# M207X.net
KiCad netlist of a schematic drawn in EAGLE
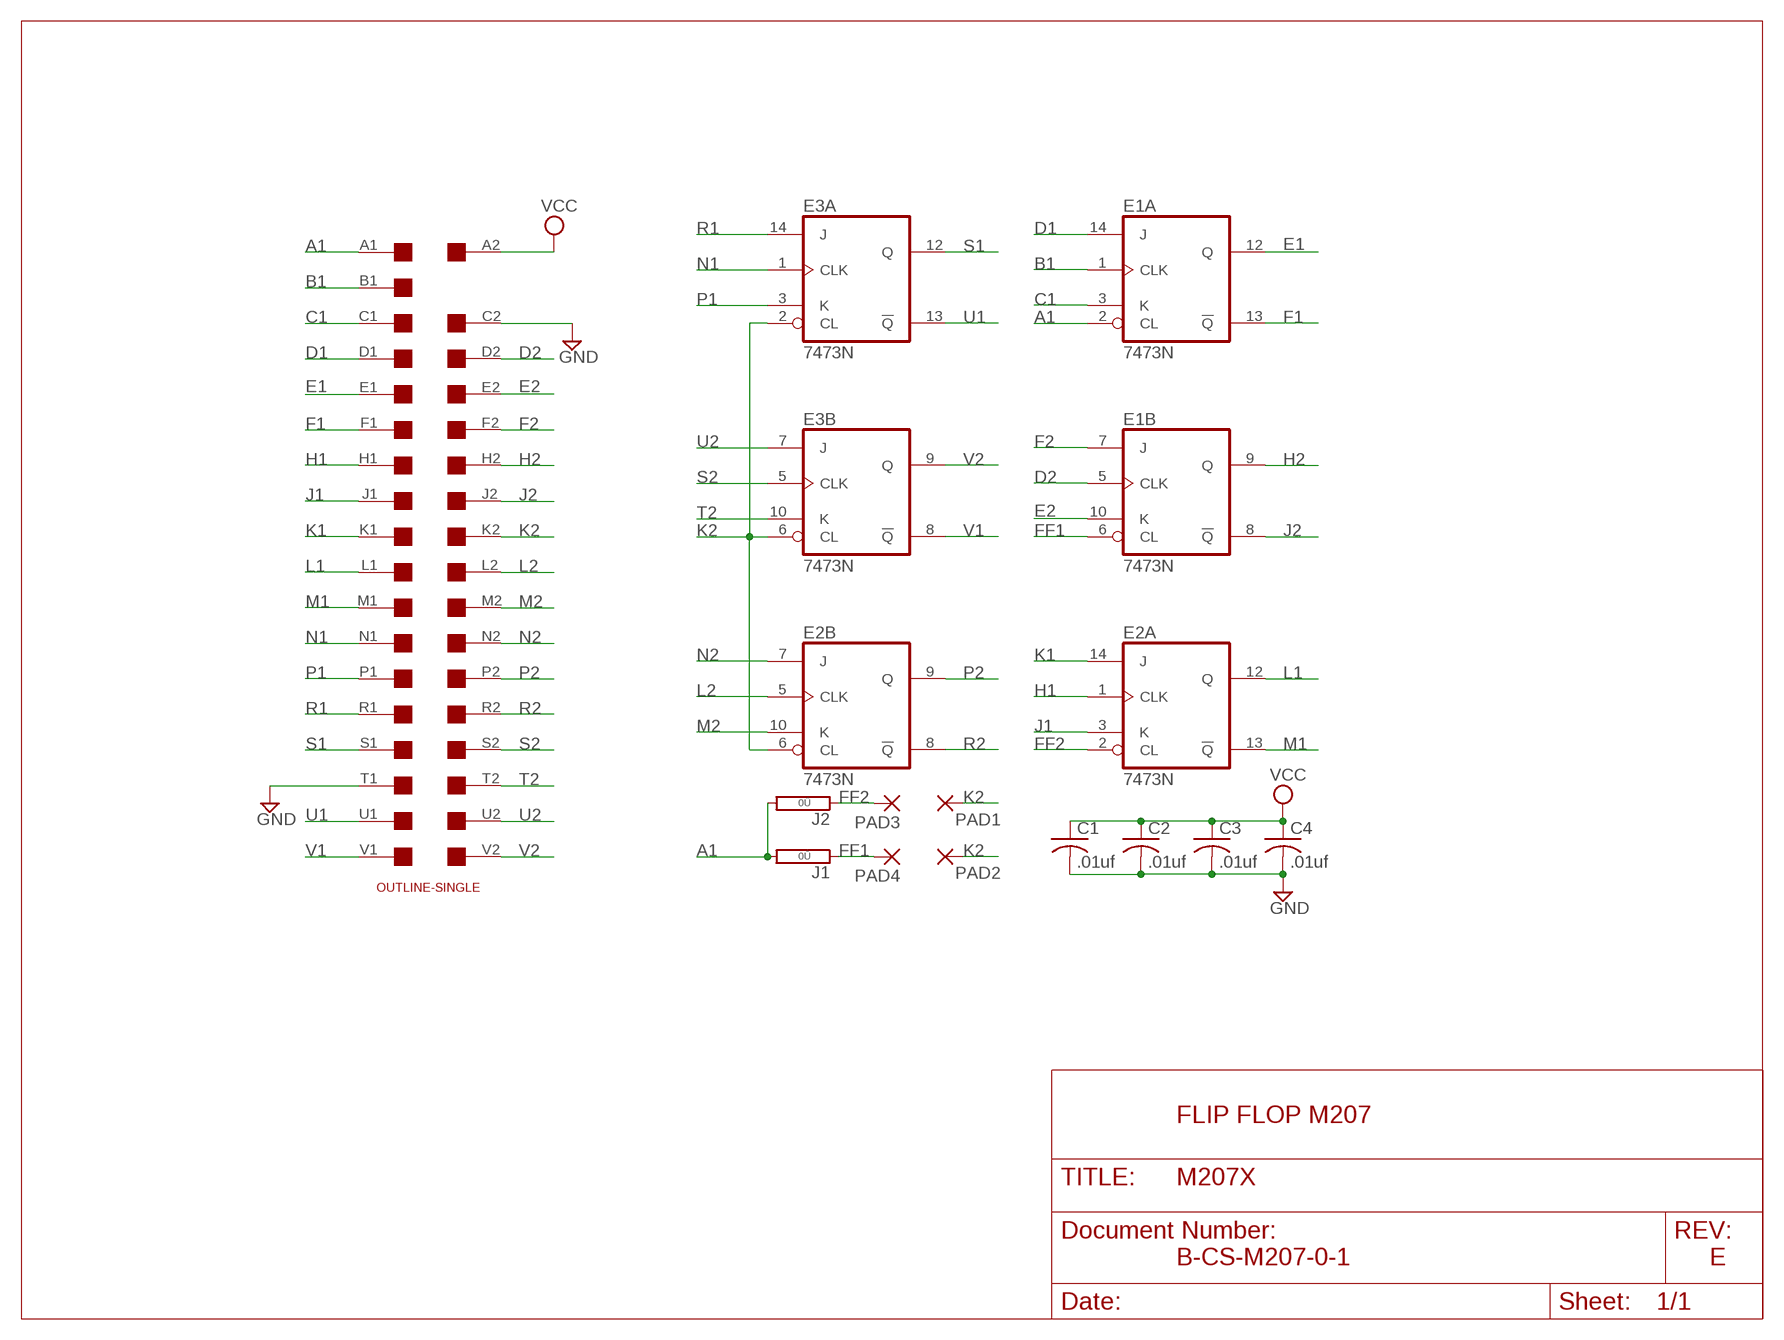
[diagram p0: schematic, sheet 1]

(export (version "E")
  (design (tool "Eeschema 10.0.6"))
  (components
    (comp (ref "C1")
      (value ".01uf")
      (footprint "eagle-import:C050-025X075")
      (libsource (lib "eagle-import") (part "C-US050-025X075"))
    )
    (comp (ref "C2")
      (value ".01uf")
      (footprint "eagle-import:C050-025X075")
      (libsource (lib "eagle-import") (part "C-US050-025X075"))
    )
    (comp (ref "C3")
      (value ".01uf")
      (footprint "eagle-import:C050-025X075")
      (libsource (lib "eagle-import") (part "C-US050-025X075"))
    )
    (comp (ref "C4")
      (value ".01uf")
      (footprint "eagle-import:C050-025X075")
      (libsource (lib "eagle-import") (part "C-US050-025X075"))
    )
    (comp (ref "E1")
      (value "7473N")
      (footprint "eagle-import:DIL14")
      (libsource (lib "eagle-import") (part "7473NLS"))
    )
    (comp (ref "E2")
      (value "7473N")
      (footprint "eagle-import:DIL14")
      (libsource (lib "eagle-import") (part "7473NLS"))
    )
    (comp (ref "E3")
      (value "7473N")
      (footprint "eagle-import:DIL14")
      (libsource (lib "eagle-import") (part "7473NLS"))
    )
    (comp (ref "J1")
      (value "0R")
      (footprint "eagle-import:0R_10")
      (libsource (lib "eagle-import") (part "0R"))
    )
    (comp (ref "J2")
      (value "0R")
      (footprint "eagle-import:0R_10")
      (libsource (lib "eagle-import") (part "0R"))
    )
    (comp (ref "PAD1")
      (value "1,6/0,8")
      (footprint "eagle-import:1,6_0,8")
      (libsource (lib "eagle-import") (part "1,6/0,8"))
    )
    (comp (ref "PAD2")
      (value "1,6/0,8")
      (footprint "eagle-import:1,6_0,8")
      (libsource (lib "eagle-import") (part "1,6/0,8"))
    )
    (comp (ref "PAD3")
      (value "1,6/0,8")
      (footprint "eagle-import:1,6_0,8")
      (libsource (lib "eagle-import") (part "1,6/0,8"))
    )
    (comp (ref "PAD4")
      (value "1,6/0,8")
      (footprint "eagle-import:1,6_0,8")
      (libsource (lib "eagle-import") (part "1,6/0,8"))
    )
    (comp (ref "U$1")
      (value "SINGLE")
      (footprint "eagle-import:EDGE-CON2")
      (libsource (lib "eagle-import") (part "SINGLE"))
    )
    (comp (ref "U$4")
      (value "OUTLINE-SINGLE")
      (footprint "eagle-import:SINGLE")
      (libsource (lib "eagle-import") (part "OUTLINE-SINGLE"))
    )
  )
  (nets
    (net (code "1") (name "/A1") (class "Default")
      (node (ref "E1") (pin "2") (pinfunction "CL_2") (pintype "input"))
      (node (ref "J1") (pin "2") (pinfunction "2_2") (pintype "passive"))
      (node (ref "J2") (pin "2") (pinfunction "2_2") (pintype "passive"))
      (node (ref "U$1") (pin "A1") (pinfunction "1_A1") (pintype "bidirectional"))
    )
    (net (code "2") (name "/B1") (class "Default")
      (node (ref "E1") (pin "1") (pinfunction "CLK_1") (pintype "input"))
      (node (ref "U$1") (pin "B1") (pinfunction "1_B1") (pintype "bidirectional"))
    )
    (net (code "3") (name "/C1") (class "Default")
      (node (ref "E1") (pin "3") (pinfunction "K_3") (pintype "input"))
      (node (ref "U$1") (pin "C1") (pinfunction "1_C1") (pintype "bidirectional"))
    )
    (net (code "4") (name "/D1") (class "Default")
      (node (ref "E1") (pin "14") (pinfunction "J_14") (pintype "input"))
      (node (ref "U$1") (pin "D1") (pinfunction "1_D1") (pintype "bidirectional"))
    )
    (net (code "5") (name "/D2") (class "Default")
      (node (ref "E1") (pin "5") (pinfunction "CLK_5") (pintype "input"))
      (node (ref "U$1") (pin "D2") (pinfunction "1_D2") (pintype "bidirectional"))
    )
    (net (code "6") (name "/E1") (class "Default")
      (node (ref "E1") (pin "12") (pinfunction "Q_12") (pintype "output"))
      (node (ref "U$1") (pin "E1") (pinfunction "1_E1") (pintype "bidirectional"))
    )
    (net (code "7") (name "/E2") (class "Default")
      (node (ref "E1") (pin "10") (pinfunction "K_10") (pintype "input"))
      (node (ref "U$1") (pin "E2") (pinfunction "1_E2") (pintype "bidirectional"))
    )
    (net (code "8") (name "/F1") (class "Default")
      (node (ref "E1") (pin "13") (pinfunction "~{Q}_13") (pintype "output"))
      (node (ref "U$1") (pin "F1") (pinfunction "1_F1") (pintype "bidirectional"))
    )
    (net (code "9") (name "/F2") (class "Default")
      (node (ref "E1") (pin "7") (pinfunction "J_7") (pintype "input"))
      (node (ref "U$1") (pin "F2") (pinfunction "1_F2") (pintype "bidirectional"))
    )
    (net (code "10") (name "/FF1") (class "Default")
      (node (ref "E1") (pin "6") (pinfunction "CL_6") (pintype "input"))
      (node (ref "J1") (pin "1") (pinfunction "1_1") (pintype "passive"))
      (node (ref "PAD4") (pin "1") (pinfunction "P_1") (pintype "passive"))
    )
    (net (code "11") (name "/FF2") (class "Default")
      (node (ref "E2") (pin "2") (pinfunction "CL_2") (pintype "input"))
      (node (ref "J2") (pin "1") (pinfunction "1_1") (pintype "passive"))
      (node (ref "PAD3") (pin "1") (pinfunction "P_1") (pintype "passive"))
    )
    (net (code "12") (name "/H1") (class "Default")
      (node (ref "E2") (pin "1") (pinfunction "CLK_1") (pintype "input"))
      (node (ref "U$1") (pin "H1") (pinfunction "1_H1") (pintype "bidirectional"))
    )
    (net (code "13") (name "/H2") (class "Default")
      (node (ref "E1") (pin "9") (pinfunction "Q_9") (pintype "output"))
      (node (ref "U$1") (pin "H2") (pinfunction "1_H2") (pintype "bidirectional"))
    )
    (net (code "14") (name "/J1") (class "Default")
      (node (ref "E2") (pin "3") (pinfunction "K_3") (pintype "input"))
      (node (ref "U$1") (pin "J1") (pinfunction "1_J1") (pintype "bidirectional"))
    )
    (net (code "15") (name "/J2") (class "Default")
      (node (ref "E1") (pin "8") (pinfunction "~{Q}_8") (pintype "output"))
      (node (ref "U$1") (pin "J2") (pinfunction "1_J2") (pintype "bidirectional"))
    )
    (net (code "16") (name "/K1") (class "Default")
      (node (ref "E2") (pin "14") (pinfunction "J_14") (pintype "input"))
      (node (ref "U$1") (pin "K1") (pinfunction "1_K1") (pintype "bidirectional"))
    )
    (net (code "17") (name "/K2") (class "Default")
      (node (ref "E2") (pin "6") (pinfunction "CL_6") (pintype "input"))
      (node (ref "E3") (pin "2") (pinfunction "CL_2") (pintype "input"))
      (node (ref "E3") (pin "6") (pinfunction "CL_6") (pintype "input"))
      (node (ref "PAD1") (pin "1") (pinfunction "P_1") (pintype "passive"))
      (node (ref "PAD2") (pin "1") (pinfunction "P_1") (pintype "passive"))
      (node (ref "U$1") (pin "K2") (pinfunction "1_K2") (pintype "bidirectional"))
    )
    (net (code "18") (name "/L1") (class "Default")
      (node (ref "E2") (pin "12") (pinfunction "Q_12") (pintype "output"))
      (node (ref "U$1") (pin "L1") (pinfunction "1_L1") (pintype "bidirectional"))
    )
    (net (code "19") (name "/L2") (class "Default")
      (node (ref "E2") (pin "5") (pinfunction "CLK_5") (pintype "input"))
      (node (ref "U$1") (pin "L2") (pinfunction "1_L2") (pintype "bidirectional"))
    )
    (net (code "20") (name "/M1") (class "Default")
      (node (ref "E2") (pin "13") (pinfunction "~{Q}_13") (pintype "output"))
      (node (ref "U$1") (pin "M1") (pinfunction "1_M1") (pintype "bidirectional"))
    )
    (net (code "21") (name "/M2") (class "Default")
      (node (ref "E2") (pin "10") (pinfunction "K_10") (pintype "input"))
      (node (ref "U$1") (pin "M2") (pinfunction "1_M2") (pintype "bidirectional"))
    )
    (net (code "22") (name "/N1") (class "Default")
      (node (ref "E3") (pin "1") (pinfunction "CLK_1") (pintype "input"))
      (node (ref "U$1") (pin "N1") (pinfunction "1_N1") (pintype "bidirectional"))
    )
    (net (code "23") (name "/N2") (class "Default")
      (node (ref "E2") (pin "7") (pinfunction "J_7") (pintype "input"))
      (node (ref "U$1") (pin "N2") (pinfunction "1_N2") (pintype "bidirectional"))
    )
    (net (code "24") (name "/P1") (class "Default")
      (node (ref "E3") (pin "3") (pinfunction "K_3") (pintype "input"))
      (node (ref "U$1") (pin "P1") (pinfunction "1_P1") (pintype "bidirectional"))
    )
    (net (code "25") (name "/P2") (class "Default")
      (node (ref "E2") (pin "9") (pinfunction "Q_9") (pintype "output"))
      (node (ref "U$1") (pin "P2") (pinfunction "1_P2") (pintype "bidirectional"))
    )
    (net (code "26") (name "/R1") (class "Default")
      (node (ref "E3") (pin "14") (pinfunction "J_14") (pintype "input"))
      (node (ref "U$1") (pin "R1") (pinfunction "1_R1") (pintype "bidirectional"))
    )
    (net (code "27") (name "/R2") (class "Default")
      (node (ref "E2") (pin "8") (pinfunction "~{Q}_8") (pintype "output"))
      (node (ref "U$1") (pin "R2") (pinfunction "1_R2") (pintype "bidirectional"))
    )
    (net (code "28") (name "/S1") (class "Default")
      (node (ref "E3") (pin "12") (pinfunction "Q_12") (pintype "output"))
      (node (ref "U$1") (pin "S1") (pinfunction "1_S1") (pintype "bidirectional"))
    )
    (net (code "29") (name "/S2") (class "Default")
      (node (ref "E3") (pin "5") (pinfunction "CLK_5") (pintype "input"))
      (node (ref "U$1") (pin "S2") (pinfunction "1_S2") (pintype "bidirectional"))
    )
    (net (code "30") (name "/T2") (class "Default")
      (node (ref "E3") (pin "10") (pinfunction "K_10") (pintype "input"))
      (node (ref "U$1") (pin "T2") (pinfunction "1_T2") (pintype "bidirectional"))
    )
    (net (code "31") (name "/U1") (class "Default")
      (node (ref "E3") (pin "13") (pinfunction "~{Q}_13") (pintype "output"))
      (node (ref "U$1") (pin "U1") (pinfunction "1_U1") (pintype "bidirectional"))
    )
    (net (code "32") (name "/U2") (class "Default")
      (node (ref "E3") (pin "7") (pinfunction "J_7") (pintype "input"))
      (node (ref "U$1") (pin "U2") (pinfunction "1_U2") (pintype "bidirectional"))
    )
    (net (code "33") (name "/V1") (class "Default")
      (node (ref "E3") (pin "8") (pinfunction "~{Q}_8") (pintype "output"))
      (node (ref "U$1") (pin "V1") (pinfunction "1_V1") (pintype "bidirectional"))
    )
    (net (code "34") (name "/V2") (class "Default")
      (node (ref "E3") (pin "9") (pinfunction "Q_9") (pintype "output"))
      (node (ref "U$1") (pin "V2") (pinfunction "1_V2") (pintype "bidirectional"))
    )
    (net (code "35") (name "GND") (class "Default")
      (node (ref "C1") (pin "2") (pinfunction "2_2") (pintype "passive"))
      (node (ref "C2") (pin "2") (pinfunction "2_2") (pintype "passive"))
      (node (ref "C3") (pin "2") (pinfunction "2_2") (pintype "passive"))
      (node (ref "C4") (pin "2") (pinfunction "2_2") (pintype "passive"))
      (node (ref "U$1") (pin "C2") (pinfunction "1_C2") (pintype "bidirectional"))
      (node (ref "U$1") (pin "T1") (pinfunction "1_T1") (pintype "bidirectional"))
    )
    (net (code "36") (name "VCC") (class "Default")
      (node (ref "C1") (pin "1") (pinfunction "1_1") (pintype "passive"))
      (node (ref "C2") (pin "1") (pinfunction "1_1") (pintype "passive"))
      (node (ref "C3") (pin "1") (pinfunction "1_1") (pintype "passive"))
      (node (ref "C4") (pin "1") (pinfunction "1_1") (pintype "passive"))
      (node (ref "U$1") (pin "A2") (pinfunction "1_A2") (pintype "bidirectional"))
    )
  )
)
